# NRF_Module.net
KiCad netlist of a schematic drawn in Altium Designer
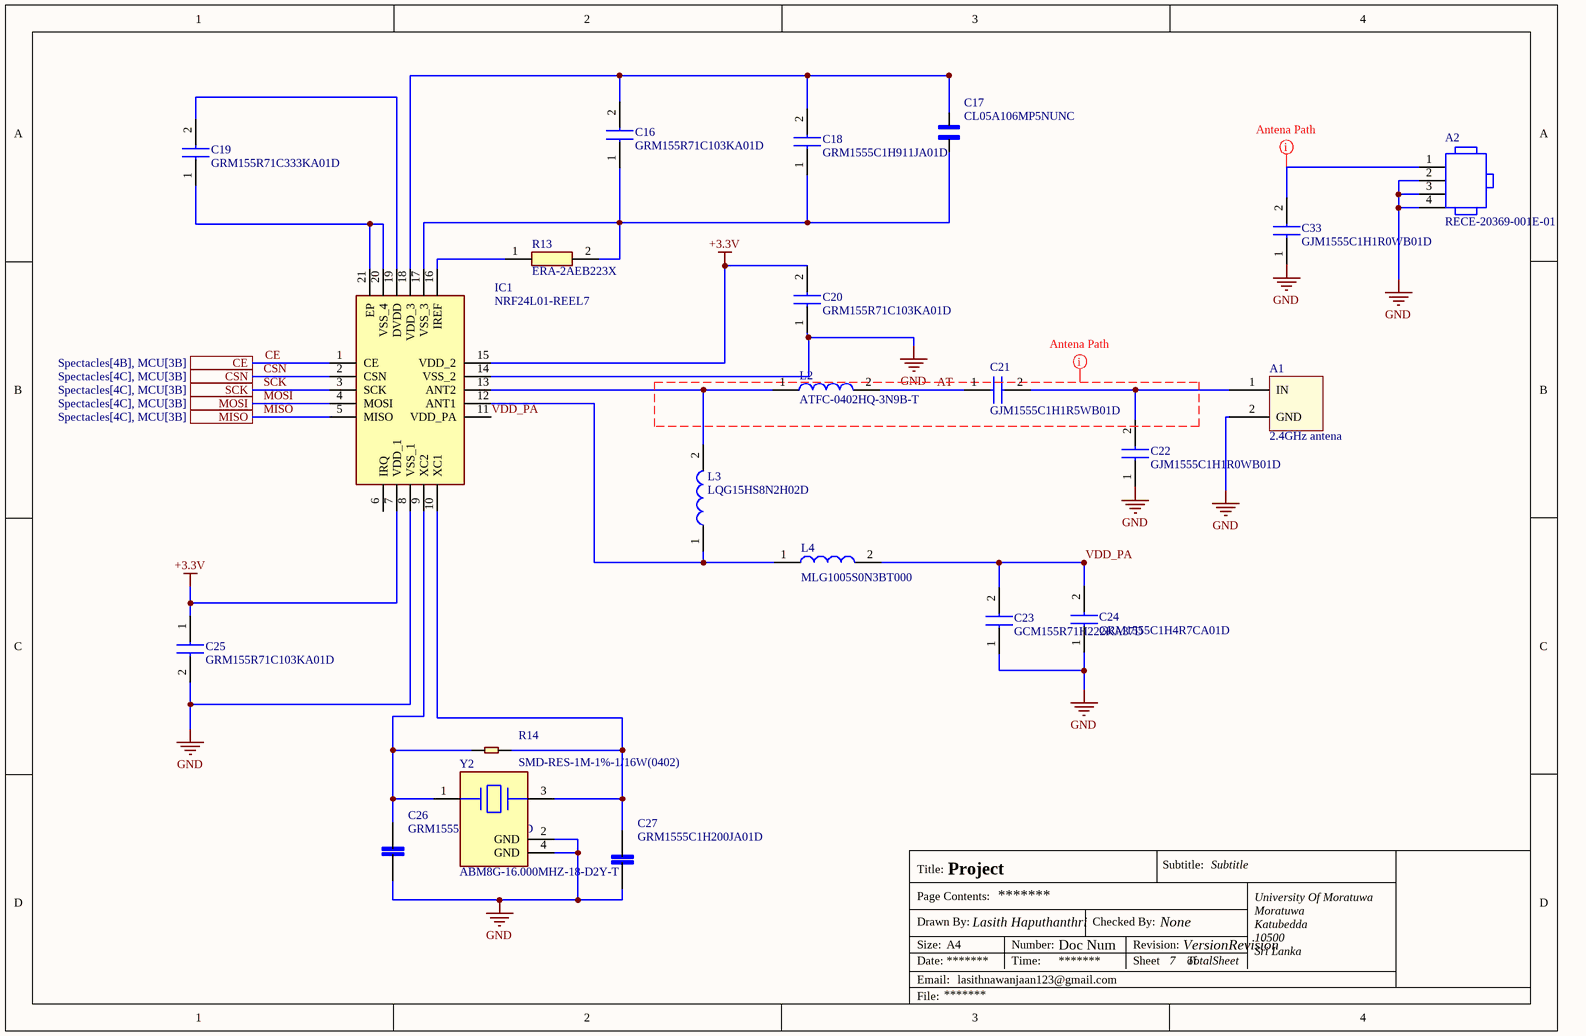
[diagram p0: NRF Module.SchDoc]

(export (version "E")
  (design (tool "Eeschema 10.0.6"))
  (components
    (comp (ref "A1")
      (value "2.4GHz antena")
      (footprint "Antena")
      (libsource (lib "Schlib1") (part "2.4GHz antena"))
    )
    (comp (ref "A2")
      (value "RECE-20369-001E-01")
      (footprint "TG-RECE-20369-001E-4_V")
      (description "RF Connector, Onboard Receptacle, IPEX MHFIII")
      (fields (field (name "MANUFACTURER") "Taoglas"))
      (libsource (lib "Altium Content Vault") (part "TG-RECE-20369-001E-01-4"))
    )
    (comp (ref "C16")
      (value "GRM155R71C103KA01D")
      (footprint "SamacSys:CAPC1005X55N")
      (description "Capacitor")
      (fields (field (name "MOUSER PART NUMBER") "81-GRM36X103K16"))
      (libsource (lib "*") (part "GRM155R71C103KA01D"))
    )
    (comp (ref "C17")
      (value "CL05A106MP5NUNC")
      (footprint "CAPC1005X55N")
      (description "10 ÂµF Â±20% 10V Ceramic Capacitor X5R 0402 (1005 Metric)")
      (fields (field (name "MF") "Samsung Electro-Mechanics"))
      (libsource (lib "CL05A106MP5NUNC") (part "CL05A106MP5NUNC"))
    )
    (comp (ref "C18")
      (value "GRM1555C1H911JA01D")
      (footprint "SamacSys:CAPC1005X55N")
      (description "Capacitor")
      (fields (field (name "MOUSER PART NUMBER") "81-GRM1555C1H911JA1D"))
      (libsource (lib "*") (part "GRM1555C1H911JA01D"))
    )
    (comp (ref "C19")
      (value "GRM155R71C333KA01D")
      (footprint "SamacSys:CAPC1005X55N")
      (description "Capacitor")
      (libsource (lib "*") (part "GRM155R71C333KA01D"))
    )
    (comp (ref "C20")
      (value "GRM155R71C103KA01D")
      (footprint "SamacSys:CAPC1005X55N")
      (description "Capacitor")
      (fields (field (name "MOUSER PART NUMBER") "81-GRM36X103K16"))
      (libsource (lib "*") (part "GRM155R71C103KA01D"))
    )
    (comp (ref "C21")
      (value "GJM1555C1H1R5WB01D")
      (footprint "SamacSys:CAPC1005X55N")
      (description "Capacitor")
      (fields (field (name "MOUSER PART NUMBER") "81-GJM1555C1H1R5WB1D"))
      (libsource (lib "*") (part "GJM1555C1H1R5WB01D"))
    )
    (comp (ref "C22")
      (value "GJM1555C1H1R0WB01D")
      (footprint "SamacSys:CAPC1005X55N")
      (description "Capacitor")
      (fields (field (name "MOUSER PART NUMBER") "81-GJM1555C1H1R0WB1D"))
      (libsource (lib "*") (part "GJM1555C1H1R0WB01D"))
    )
    (comp (ref "C23")
      (value "GCM155R71H222KA37D")
      (footprint "SamacSys:CAPC1005X55N")
      (description "Capacitor")
      (fields (field (name "MOUSER PART NUMBER") "81-GCM155R71H222K37D"))
      (libsource (lib "*") (part "GCM155R71H222KA37D"))
    )
    (comp (ref "C24")
      (value "GRM1555C1H4R7CA01D")
      (footprint "SamacSys:CAPC1005X55N")
      (description "Capacitor")
      (fields (field (name "MOUSER PART NUMBER") "81-GRM1555C1H4R7CA1D"))
      (libsource (lib "*") (part "GRM1555C1H4R7CA01D"))
    )
    (comp (ref "C25")
      (value "GRM155R71C103KA01D")
      (footprint "SamacSys:CAPC1005X55N")
      (description "Capacitor")
      (fields (field (name "MOUSER PART NUMBER") "81-GRM36X103K16"))
      (libsource (lib "*") (part "GRM155R71C103KA01D"))
    )
    (comp (ref "C26")
      (value "GRM1555C1H200JA01D")
      (footprint "CAPC1005X55N")
      (description "SMD Capacitor C0G(EIA) with Capacitance: 20pF Tol. 5%. Rated Voltage: 50Vdc")
      (fields (field (name "MF") "Murata"))
      (libsource (lib "GRM1555C1H200JA01D") (part "GRM1555C1H200JA01D"))
    )
    (comp (ref "C27")
      (value "GRM1555C1H200JA01D")
      (footprint "CAPC1005X55N")
      (description "SMD Capacitor C0G(EIA) with Capacitance: 20pF Tol. 5%. Rated Voltage: 50Vdc")
      (fields (field (name "MF") "Murata"))
      (libsource (lib "GRM1555C1H200JA01D") (part "GRM1555C1H200JA01D"))
    )
    (comp (ref "C33")
      (value "GJM1555C1H1R0WB01D")
      (footprint "SamacSys:CAPC1005X55N")
      (description "Capacitor")
      (fields (field (name "MOUSER PART NUMBER") "81-GJM1555C1H1R0WB1D"))
      (libsource (lib "*") (part "GJM1555C1H1R0WB01D"))
    )
    (comp (ref "IC1")
      (value "NRF24L01-REEL7")
      (footprint "SamacSys:QFN50P400X400X80-21N-D")
      (description "Integrated Circuit")
      (fields (field (name "MOUSER PART NUMBER") "949-NRF24L01-REEL7"))
      (libsource (lib "*") (part "NRF24L01-REEL7"))
    )
    (comp (ref "L2")
      (value "ATFC-0402HQ-3N9B-T")
      (footprint "SamacSys:INDC1005X37N")
      (description "Inductor")
      (libsource (lib "*") (part "ATFC-0402HQ-3N9B-T"))
    )
    (comp (ref "L3")
      (value "LQG15HS8N2H02D")
      (footprint "SamacSys:LQG15WH0N7B02D")
      (description "Inductor")
      (fields (field (name "MOUSER PART NUMBER") "81-LQG15HS8N2H02D"))
      (libsource (lib "*") (part "LQG15HS8N2H02D"))
    )
    (comp (ref "L4")
      (value "MLG1005S0N3BT000")
      (footprint "SamacSys:MLG1005")
      (description "Inductor")
      (fields (field (name "MOUSER PART NUMBER") "810-MLG1005S0N3BT000"))
      (libsource (lib "*") (part "MLG1005S0N3BT000"))
    )
    (comp (ref "R13")
      (value "ERA-2AEB223X")
      (footprint "SamacSys:ERA2AED122X")
      (description "Resistor")
      (fields (field (name "MOUSER PART NUMBER") "667-ERA-2AEB223X"))
      (libsource (lib "*") (part "ERA-2AEB223X"))
    )
    (comp (ref "R14")
      (value "SMD-RES-1M-1%-1/16W(0402)")
      (footprint "R0402")
      (description "1 MOhms Â±1% 0.063W, 1/16W Chip Resistor 0402 (1005 Metric) Moisture Resistant Thick Film")
      (fields (field (name "MF") "Yageo") (field (name "MP") "RC0402FR-071ML"))
      (libsource (lib "SMD-RES-1M-1_-1_16W_0402_") (part "SMD-RES-1M-1%-1/16W(0402)"))
    )
    (comp (ref "Y2")
      (value "ABM8G-16.000MHZ-18-D2Y-T")
      (footprint "FP-ABM8G-MFG")
      (description "Crystal 12MHz ±20ppm (Tol) ±30ppm (Stability) 18pF FUND 120Ω 4-Pin SMD T/R")
      (fields (field (name "TOLERANCE") "20ppm"))
      (libsource (lib "Altium Content Vault") (part "48e526d86b7f2615d98721063c72f49"))
    )
  )
  (nets
    (net (code "1") (name "+3.3V") (class "Default")
      (node (ref "C20") (pin "2") (pinfunction "2_2") (pintype "passive"))
      (node (ref "C25") (pin "1") (pinfunction "1_1") (pintype "passive"))
      (node (ref "IC1") (pin "15") (pinfunction "VDD_2_15") (pintype "passive"))
      (node (ref "IC1") (pin "7") (pinfunction "VDD_1_7") (pintype "passive"))
    )
    (net (code "2") (name "/AT") (class "Default")
      (node (ref "C21") (pin "1") (pinfunction "1_1") (pintype "passive"))
      (node (ref "L2") (pin "2") (pinfunction "2_2") (pintype "passive"))
    )
    (net (code "3") (name "/CE") (class "Default")
      (node (ref "IC1") (pin "1") (pinfunction "CE_1") (pintype "passive"))
    )
    (net (code "4") (name "/CSN") (class "Default")
      (node (ref "IC1") (pin "2") (pinfunction "CSN_2") (pintype "passive"))
    )
    (net (code "5") (name "/MISO") (class "Default")
      (node (ref "IC1") (pin "5") (pinfunction "MISO_5") (pintype "passive"))
    )
    (net (code "6") (name "/MOSI") (class "Default")
      (node (ref "IC1") (pin "4") (pinfunction "MOSI_4") (pintype "passive"))
    )
    (net (code "7") (name "/SCK") (class "Default")
      (node (ref "IC1") (pin "3") (pinfunction "SCK_3") (pintype "passive"))
    )
    (net (code "8") (name "/VDD_PA") (class "Default")
      (node (ref "C23") (pin "2") (pinfunction "2_2") (pintype "passive"))
      (node (ref "C24") (pin "2") (pinfunction "2_2") (pintype "passive"))
      (node (ref "IC1") (pin "11") (pinfunction "VDD_PA_11") (pintype "passive"))
      (node (ref "L4") (pin "2") (pinfunction "2_2") (pintype "passive"))
    )
    (net (code "9") (name "GND") (class "Default")
      (node (ref "A1") (pin "2") (pinfunction "GND_2") (pintype "passive"))
      (node (ref "A2") (pin "2") (pinfunction "2_2") (pintype "passive"))
      (node (ref "A2") (pin "3") (pinfunction "3_3") (pintype "passive"))
      (node (ref "A2") (pin "4") (pinfunction "4_4") (pintype "passive"))
      (node (ref "C20") (pin "1") (pinfunction "1_1") (pintype "passive"))
      (node (ref "C22") (pin "1") (pinfunction "1_1") (pintype "passive"))
      (node (ref "C23") (pin "1") (pinfunction "1_1") (pintype "passive"))
      (node (ref "C24") (pin "1") (pinfunction "1_1") (pintype "passive"))
      (node (ref "C25") (pin "2") (pinfunction "2_2") (pintype "passive"))
      (node (ref "C26") (pin "1") (pinfunction "1_1") (pintype "passive"))
      (node (ref "C27") (pin "1") (pinfunction "1_1") (pintype "passive"))
      (node (ref "C33") (pin "1") (pinfunction "1_1") (pintype "passive"))
      (node (ref "IC1") (pin "14") (pinfunction "VSS_2_14") (pintype "passive"))
      (node (ref "IC1") (pin "8") (pinfunction "VSS_1_8") (pintype "passive"))
      (node (ref "Y2") (pin "2") (pinfunction "GND_2") (pintype "power_in"))
      (node (ref "Y2") (pin "4") (pinfunction "GND_4") (pintype "power_in"))
    )
    (net (code "10") (name "Net-(A1-IN)") (class "Default")
      (node (ref "A1") (pin "1") (pinfunction "IN_1") (pintype "passive"))
      (node (ref "C21") (pin "2") (pinfunction "2_2") (pintype "passive"))
      (node (ref "C22") (pin "2") (pinfunction "2_2") (pintype "passive"))
    )
    (net (code "11") (name "Net-(A2-Pad1)") (class "Default")
      (node (ref "A2") (pin "1") (pinfunction "1_1") (pintype "passive"))
      (node (ref "C33") (pin "2") (pinfunction "2_2") (pintype "passive"))
    )
    (net (code "12") (name "Net-(IC1-ANT1)") (class "Default")
      (node (ref "IC1") (pin "12") (pinfunction "ANT1_12") (pintype "passive"))
      (node (ref "L3") (pin "1") (pinfunction "1_1") (pintype "passive"))
      (node (ref "L4") (pin "1") (pinfunction "1_1") (pintype "passive"))
    )
    (net (code "13") (name "Net-(IC1-ANT2)") (class "Default")
      (node (ref "IC1") (pin "13") (pinfunction "ANT2_13") (pintype "passive"))
      (node (ref "L2") (pin "1") (pinfunction "1_1") (pintype "passive"))
      (node (ref "L3") (pin "2") (pinfunction "2_2") (pintype "passive"))
    )
    (net (code "14") (name "Net-(IC1-DVDD)") (class "Default")
      (node (ref "C19") (pin "2") (pinfunction "2_2") (pintype "passive"))
      (node (ref "IC1") (pin "19") (pinfunction "DVDD_19") (pintype "passive"))
    )
    (net (code "15") (name "Net-(IC1-EP)") (class "Default")
      (node (ref "C19") (pin "1") (pinfunction "1_1") (pintype "passive"))
      (node (ref "IC1") (pin "20") (pinfunction "VSS_4_20") (pintype "passive"))
      (node (ref "IC1") (pin "21") (pinfunction "EP_21") (pintype "passive"))
    )
    (net (code "16") (name "Net-(IC1-IREF)") (class "Default")
      (node (ref "IC1") (pin "16") (pinfunction "IREF_16") (pintype "passive"))
      (node (ref "R13") (pin "1") (pinfunction "1_1") (pintype "passive"))
    )
    (net (code "17") (name "Net-(IC1-VDD_3)") (class "Default")
      (node (ref "C16") (pin "2") (pinfunction "2_2") (pintype "passive"))
      (node (ref "C17") (pin "2") (pinfunction "2_2") (pintype "passive"))
      (node (ref "C18") (pin "2") (pinfunction "2_2") (pintype "passive"))
      (node (ref "IC1") (pin "18") (pinfunction "VDD_3_18") (pintype "passive"))
    )
    (net (code "18") (name "Net-(IC1-VSS_3)") (class "Default")
      (node (ref "C16") (pin "1") (pinfunction "1_1") (pintype "passive"))
      (node (ref "C17") (pin "1") (pinfunction "1_1") (pintype "passive"))
      (node (ref "C18") (pin "1") (pinfunction "1_1") (pintype "passive"))
      (node (ref "IC1") (pin "17") (pinfunction "VSS_3_17") (pintype "passive"))
      (node (ref "R13") (pin "2") (pinfunction "2_2") (pintype "passive"))
    )
    (net (code "19") (name "Net-(IC1-XC1)") (class "Default")
      (node (ref "C27") (pin "2") (pinfunction "2_2") (pintype "passive"))
      (node (ref "IC1") (pin "10") (pinfunction "XC1_10") (pintype "passive"))
      (node (ref "R14") (pin "2") (pinfunction "2_2") (pintype "passive"))
      (node (ref "Y2") (pin "3") (pinfunction "3_3") (pintype "passive"))
    )
    (net (code "20") (name "Net-(IC1-XC2)") (class "Default")
      (node (ref "C26") (pin "2") (pinfunction "2_2") (pintype "passive"))
      (node (ref "IC1") (pin "9") (pinfunction "XC2_9") (pintype "passive"))
      (node (ref "R14") (pin "1") (pinfunction "1_1") (pintype "passive"))
      (node (ref "Y2") (pin "1") (pinfunction "1_1") (pintype "passive"))
    )
    (net (code "21") (name "unconnected-(IC1-IRQ-Pad6)") (class "Default")
      (node (ref "IC1") (pin "6") (pinfunction "IRQ_6") (pintype "passive"))
    )
  )
)
